# Sheet2.net
KiCad netlist of a schematic drawn in Altium Designer
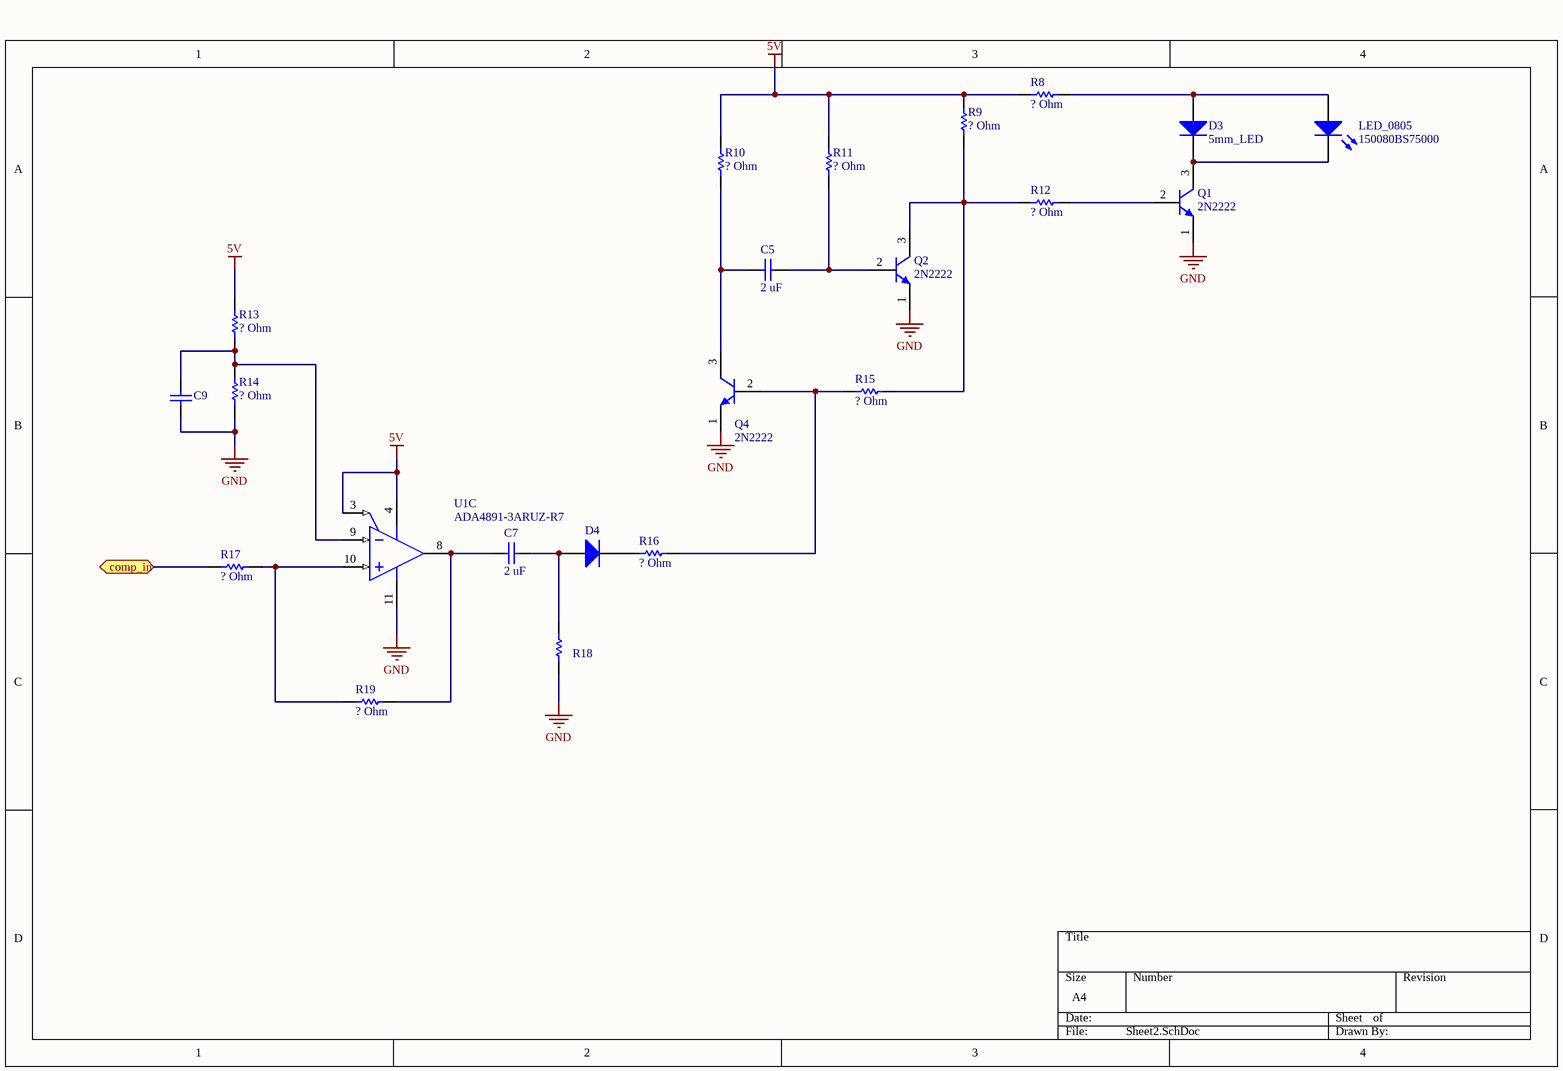
[diagram p0: Sheet2.SchDoc]

(export (version "E")
  (design (tool "Eeschema 10.0.6"))
  (components
    (comp (ref "C5")
      (value "2 uF")
      (footprint "CAPC0805(2012)75_M")
      (description "CAP 0.5pF 50V ±0.1pF 0805 (2012 Metric) Thickness 0.75mm SMD")
      (fields (field (name "TOLERANCE") "Â±0.1pF"))
      (libsource (lib "Altium Content Vault") (part "CAP"))
    )
    (comp (ref "C7")
      (value "2 uF")
      (footprint "CAPC0805(2012)75_M")
      (description "CAP 0.5pF 50V ±0.1pF 0805 (2012 Metric) Thickness 0.75mm SMD")
      (fields (field (name "TOLERANCE") "Â±0.1pF"))
      (libsource (lib "Altium Content Vault") (part "CAP"))
    )
    (comp (ref "C9")
      (value "CAP 0.5pF 50V 0805(2012)")
      (footprint "CAPC0805(2012)75_M")
      (description "CAP 0.5pF 50V ±0.1pF 0805 (2012 Metric) Thickness 0.75mm SMD")
      (fields (field (name "TOLERANCE") "Â±0.1pF"))
      (libsource (lib "Altium Content Vault") (part "CMP-1036-00018-1"))
    )
    (comp (ref "D3")
      (value "5mm_LED")
      (footprint "3mm_diode")
      (libsource (lib "HeartbeatLibrary") (part "5mm_LED"))
    )
    (comp (ref "D4")
      (value "~")
      (footprint "DIOD-S1M-13-F-SMA-2_V")
      (fields (field (name "MANUFACTURER") "Diodes Inc") (field (name "PARTNUMBER") "S1M-13-F"))
      (libsource (lib "Altium Content Vault") (part "DIOD-D-A1K2-2"))
    )
    (comp (ref "LED_0805")
      (value "150080BS75000")
      (footprint "0805_A")
      (description "SMD mono-color Chip LED, WL-SMCW, Blue")
      (fields (field (name "MANUFACTURER") "Wuerth Elektronik"))
      (libsource (lib "Altium Content Vault") (part "WE-LED_K1A2-2"))
    )
    (comp (ref "Q1")
      (value "2N2222")
      (footprint "MLTC-TO-18-3")
      (description "Low Power Bipolar NPN Transistor, 30 V, -65 to 200 degC, 3-Pin TO-18, RoHS, Bulk")
      (fields (field (name "MANUFACTURER") "Multicomp"))
      (libsource (lib "Altium Content Vault") (part "BJT-NPN-EBC-3"))
    )
    (comp (ref "Q2")
      (value "2N2222")
      (footprint "MLTC-TO-18-3")
      (description "Low Power Bipolar NPN Transistor, 30 V, -65 to 200 degC, 3-Pin TO-18, RoHS, Bulk")
      (fields (field (name "MANUFACTURER") "Multicomp"))
      (libsource (lib "Altium Content Vault") (part "BJT-NPN-EBC-3"))
    )
    (comp (ref "Q4")
      (value "2N2222")
      (footprint "MLTC-TO-18-3")
      (description "Low Power Bipolar NPN Transistor, 30 V, -65 to 200 degC, 3-Pin TO-18, RoHS, Bulk")
      (fields (field (name "MANUFACTURER") "Multicomp"))
      (libsource (lib "Altium Content Vault") (part "BJT-NPN-EBC-3"))
    )
    (comp (ref "R8")
      (value "? Ohm")
      (footprint "RESC0805(2012)_M")
      (description "4R3 0.125W 5% 0805 (2012 Metric)  SMD")
      (fields (field (name "TOLERANCE") "5 %") (field (name "POWER") "0.125 W"))
      (libsource (lib "Altium Content Vault") (part "RES"))
    )
    (comp (ref "R9")
      (value "? Ohm")
      (footprint "RESC0805(2012)_M")
      (description "4R3 0.125W 5% 0805 (2012 Metric)  SMD")
      (fields (field (name "TOLERANCE") "5 %") (field (name "POWER") "0.125 W"))
      (libsource (lib "Altium Content Vault") (part "RES"))
    )
    (comp (ref "R10")
      (value "? Ohm")
      (footprint "RESC0805(2012)_M")
      (description "4R3 0.125W 5% 0805 (2012 Metric)  SMD")
      (fields (field (name "TOLERANCE") "5 %") (field (name "POWER") "0.125 W"))
      (libsource (lib "Altium Content Vault") (part "CMP-1013-00017-1"))
    )
    (comp (ref "R11")
      (value "? Ohm")
      (footprint "RESC0805(2012)_M")
      (description "4R3 0.125W 5% 0805 (2012 Metric)  SMD")
      (fields (field (name "TOLERANCE") "5 %") (field (name "POWER") "0.125 W"))
      (libsource (lib "Altium Content Vault") (part "RES"))
    )
    (comp (ref "R12")
      (value "? Ohm")
      (footprint "RESC0805(2012)_M")
      (description "4R3 0.125W 5% 0805 (2012 Metric)  SMD")
      (fields (field (name "TOLERANCE") "5 %") (field (name "POWER") "0.125 W"))
      (libsource (lib "Altium Content Vault") (part "RES"))
    )
    (comp (ref "R13")
      (value "? Ohm")
      (footprint "RESC0805(2012)_M")
      (description "4R3 0.125W 5% 0805 (2012 Metric)  SMD")
      (fields (field (name "TOLERANCE") "5 %") (field (name "POWER") "0.125 W"))
      (libsource (lib "Altium Content Vault") (part "RES"))
    )
    (comp (ref "R14")
      (value "? Ohm")
      (footprint "RESC0805(2012)_M")
      (description "4R3 0.125W 5% 0805 (2012 Metric)  SMD")
      (fields (field (name "TOLERANCE") "5 %") (field (name "POWER") "0.125 W"))
      (libsource (lib "Altium Content Vault") (part "RES"))
    )
    (comp (ref "R15")
      (value "? Ohm")
      (footprint "RESC0805(2012)_M")
      (description "4R3 0.125W 5% 0805 (2012 Metric)  SMD")
      (fields (field (name "TOLERANCE") "5 %") (field (name "POWER") "0.125 W"))
      (libsource (lib "Altium Content Vault") (part "RES"))
    )
    (comp (ref "R16")
      (value "? Ohm")
      (footprint "RESC0805(2012)_M")
      (description "4R3 0.125W 5% 0805 (2012 Metric)  SMD")
      (fields (field (name "TOLERANCE") "5 %") (field (name "POWER") "0.125 W"))
      (libsource (lib "Altium Content Vault") (part "CMP-1013-00017-1"))
    )
    (comp (ref "R17")
      (value "? Ohm")
      (footprint "RESC0805(2012)_M")
      (description "4R3 0.125W 5% 0805 (2012 Metric)  SMD")
      (fields (field (name "TOLERANCE") "5 %") (field (name "POWER") "0.125 W"))
      (libsource (lib "Altium Content Vault") (part "RES"))
    )
    (comp (ref "R18")
      (value "~")
      (footprint "RESC0805(2012)_M")
      (description "4R3 0.125W 5% 0805 (2012 Metric)  SMD")
      (fields (field (name "TOLERANCE") "5 %") (field (name "POWER") "0.125 W"))
      (libsource (lib "Altium Content Vault") (part "CMP-1013-00017-1"))
    )
    (comp (ref "R19")
      (value "? Ohm")
      (footprint "RESC0805(2012)_M")
      (description "4R3 0.125W 5% 0805 (2012 Metric)  SMD")
      (fields (field (name "TOLERANCE") "5 %") (field (name "POWER") "0.125 W"))
      (libsource (lib "Altium Content Vault") (part "RES"))
    )
    (comp (ref "U1")
      (value "ADA4891-3ARUZ-R7")
      (footprint "ADI-RU-14_L")
      (fields (field (name "GENERIC PART NUMBER") "ADA4891-3") (field (name "MANUFACTURER") "Analog Devices"))
      (libsource (lib "Altium Content Vault") (part "CMP-0384-01869-1"))
    )
  )
  (nets
    (net (code "1") (name "/comp_in") (class "Default")
      (node (ref "R17") (pin "2") (pinfunction "2_2") (pintype "passive"))
    )
    (net (code "2") (name "5V") (class "Default")
      (node (ref "R10") (pin "1") (pinfunction "1_1") (pintype "passive"))
      (node (ref "R11") (pin "1") (pinfunction "1_1") (pintype "passive"))
      (node (ref "R13") (pin "2") (pinfunction "2_2") (pintype "passive"))
      (node (ref "R8") (pin "1") (pinfunction "1_1") (pintype "passive"))
      (node (ref "R9") (pin "1") (pinfunction "1_1") (pintype "passive"))
      (node (ref "U1") (pin "3") (pinfunction "~{PD3}_3") (pintype "input"))
      (node (ref "U1") (pin "4") (pinfunction "+VS_4") (pintype "power_in"))
    )
    (net (code "3") (name "GND") (class "Default")
      (node (ref "C9") (pin "1") (pinfunction "1_1") (pintype "passive"))
      (node (ref "Q1") (pin "1") (pinfunction "E_1") (pintype "passive"))
      (node (ref "Q2") (pin "1") (pinfunction "E_1") (pintype "passive"))
      (node (ref "Q4") (pin "1") (pinfunction "E_1") (pintype "passive"))
      (node (ref "R14") (pin "2") (pinfunction "2_2") (pintype "passive"))
      (node (ref "R18") (pin "2") (pinfunction "2_2") (pintype "passive"))
      (node (ref "U1") (pin "11") (pinfunction "-VS_11") (pintype "power_in"))
    )
    (net (code "4") (name "Net-(D3-A)") (class "Default")
      (node (ref "D3") (pin "1") (pinfunction "A_1") (pintype "passive"))
      (node (ref "LED_0805") (pin "2") (pinfunction "A_2") (pintype "passive"))
      (node (ref "R8") (pin "2") (pinfunction "2_2") (pintype "passive"))
    )
    (net (code "5") (name "Net-(D3-K)") (class "Default")
      (node (ref "D3") (pin "2") (pinfunction "K_2") (pintype "passive"))
      (node (ref "LED_0805") (pin "1") (pinfunction "K_1") (pintype "passive"))
      (node (ref "Q1") (pin "3") (pinfunction "C_3") (pintype "passive"))
    )
    (net (code "6") (name "Net-(D4-A)") (class "Default")
      (node (ref "C7") (pin "2") (pinfunction "2_2") (pintype "passive"))
      (node (ref "D4") (pin "1") (pinfunction "A_1") (pintype "passive"))
      (node (ref "R18") (pin "1") (pinfunction "1_1") (pintype "passive"))
    )
    (net (code "7") (name "Net-(D4-K)") (class "Default")
      (node (ref "D4") (pin "2") (pinfunction "K_2") (pintype "passive"))
      (node (ref "R16") (pin "1") (pinfunction "1_1") (pintype "passive"))
    )
    (net (code "8") (name "Net-(Q1-B)") (class "Default")
      (node (ref "Q1") (pin "2") (pinfunction "B_2") (pintype "passive"))
      (node (ref "R12") (pin "2") (pinfunction "2_2") (pintype "passive"))
    )
    (net (code "9") (name "Net-(Q2-B)") (class "Default")
      (node (ref "C5") (pin "1") (pinfunction "1_1") (pintype "passive"))
      (node (ref "Q2") (pin "2") (pinfunction "B_2") (pintype "passive"))
      (node (ref "R11") (pin "2") (pinfunction "2_2") (pintype "passive"))
    )
    (net (code "10") (name "Net-(Q2-C)") (class "Default")
      (node (ref "Q2") (pin "3") (pinfunction "C_3") (pintype "passive"))
      (node (ref "R12") (pin "1") (pinfunction "1_1") (pintype "passive"))
      (node (ref "R15") (pin "2") (pinfunction "2_2") (pintype "passive"))
      (node (ref "R9") (pin "2") (pinfunction "2_2") (pintype "passive"))
    )
    (net (code "11") (name "Net-(Q4-B)") (class "Default")
      (node (ref "Q4") (pin "2") (pinfunction "B_2") (pintype "passive"))
      (node (ref "R15") (pin "1") (pinfunction "1_1") (pintype "passive"))
      (node (ref "R16") (pin "2") (pinfunction "2_2") (pintype "passive"))
    )
    (net (code "12") (name "Net-(Q4-C)") (class "Default")
      (node (ref "C5") (pin "2") (pinfunction "2_2") (pintype "passive"))
      (node (ref "Q4") (pin "3") (pinfunction "C_3") (pintype "passive"))
      (node (ref "R10") (pin "2") (pinfunction "2_2") (pintype "passive"))
    )
    (net (code "13") (name "Net-(U1C-+IN_3)") (class "Default")
      (node (ref "R17") (pin "1") (pinfunction "1_1") (pintype "passive"))
      (node (ref "R19") (pin "2") (pinfunction "2_2") (pintype "passive"))
      (node (ref "U1") (pin "10") (pinfunction "+IN_3_10") (pintype "input"))
    )
    (net (code "14") (name "Net-(U1C--IN_3)") (class "Default")
      (node (ref "C9") (pin "2") (pinfunction "2_2") (pintype "passive"))
      (node (ref "R13") (pin "1") (pinfunction "1_1") (pintype "passive"))
      (node (ref "R14") (pin "1") (pinfunction "1_1") (pintype "passive"))
      (node (ref "U1") (pin "9") (pinfunction "-IN_3_9") (pintype "input"))
    )
    (net (code "15") (name "Net-(U1C-OUT_3)") (class "Default")
      (node (ref "C7") (pin "1") (pinfunction "1_1") (pintype "passive"))
      (node (ref "R19") (pin "1") (pinfunction "1_1") (pintype "passive"))
      (node (ref "U1") (pin "8") (pinfunction "OUT_3_8") (pintype "tri_state"))
    )
  )
)
